# AVR_Board_4_0_Power_Supply.net
KiCad netlist of a schematic drawn in Altium Designer
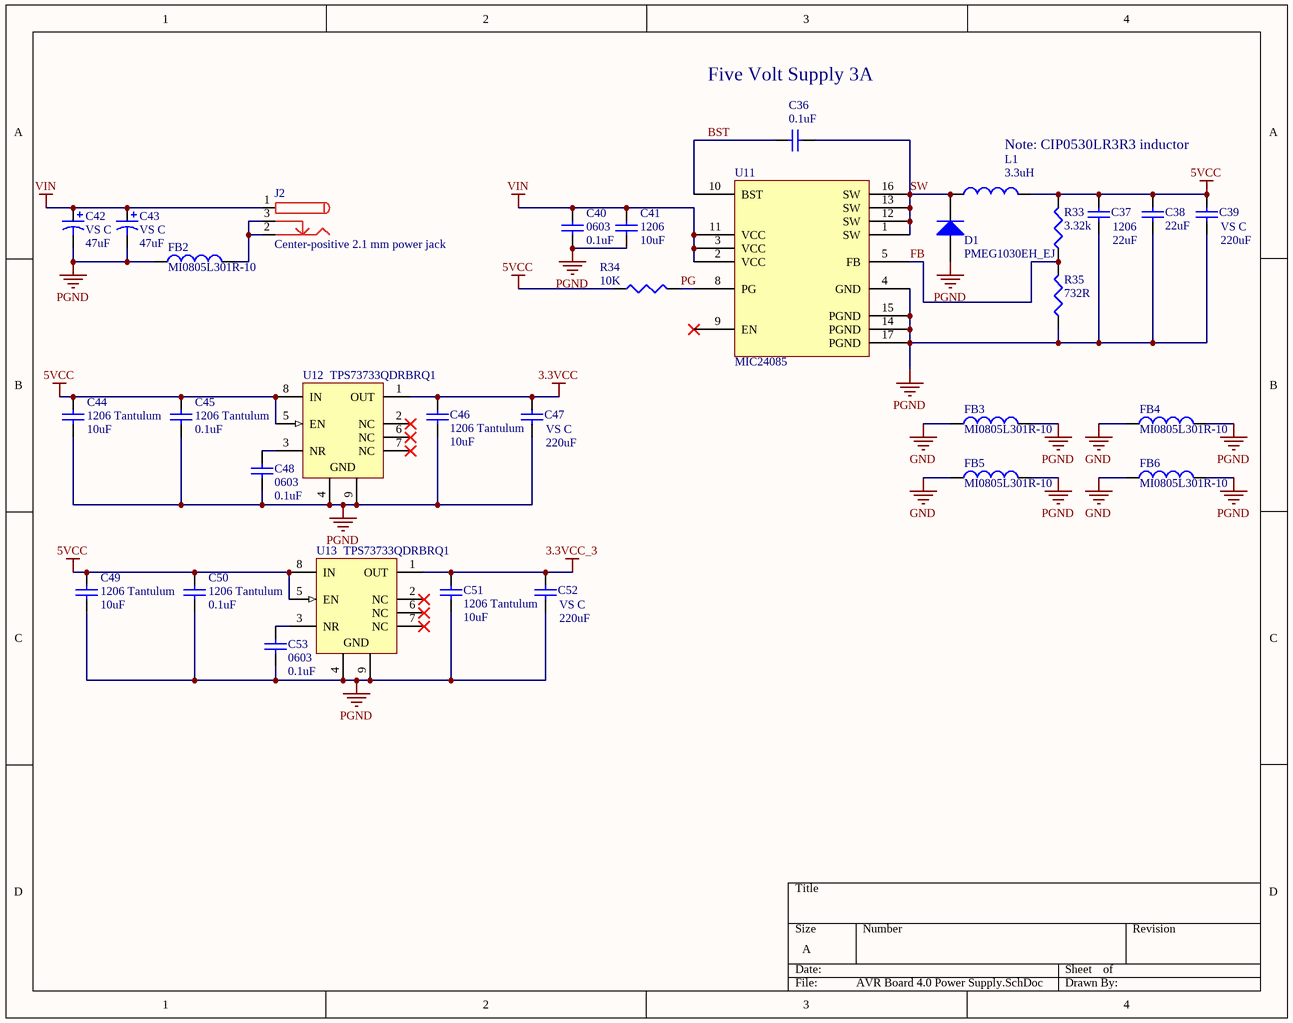
[diagram p0: AVR Board 4.0 Power Supply.SchDoc]

(export (version "E")
  (design (tool "Eeschema 10.0.6"))
  (components
    (comp (ref "C36")
      (value "0.1uF")
      (footprint "1608[0603]")
      (description "Capacitor (Semiconductor SIM Model)")
      (fields (field (name "Comment") "Cap Semi") (field (name "PUBLISHER") "Altium Limited"))
      (libsource (lib "Miscellaneous Devices") (part "Cap Semi"))
    )
    (comp (ref "C37")
      (value "1206")
      (footprint "C1206")
      (description "Capacitor (Semiconductor SIM Model)")
      (fields (field (name "ALTIUM_VALUE") "22uF") (field (name "PUBLISHER") "Altium Limited"))
      (libsource (lib "Miscellaneous Devices") (part "Cap Semi"))
    )
    (comp (ref "C38")
      (value "22uF")
      (footprint "C1206")
      (description "Capacitor (Semiconductor SIM Model)")
      (fields (field (name "Comment") "Cap Semi") (field (name "PUBLISHER") "Altium Limited"))
      (libsource (lib "Miscellaneous Devices") (part "Cap Semi"))
    )
    (comp (ref "C39")
      (value "VS C")
      (footprint "Panasonic VS C")
      (description "Capacitor (Semiconductor SIM Model)")
      (fields (field (name "ALTIUM_VALUE") "220uF") (field (name "PUBLISHER") "Altium Limited"))
      (libsource (lib "Miscellaneous Devices") (part "Cap Semi"))
    )
    (comp (ref "C40")
      (value "0603")
      (footprint "1608[0603]")
      (description "Capacitor (Semiconductor SIM Model)")
      (fields (field (name "ALTIUM_VALUE") "0.1uF") (field (name "PUBLISHER") "Altium Limited"))
      (libsource (lib "Miscellaneous Devices") (part "Cap Semi"))
    )
    (comp (ref "C41")
      (value "1206")
      (footprint "C1206")
      (description "Capacitor (Semiconductor SIM Model)")
      (fields (field (name "ALTIUM_VALUE") "10uF") (field (name "PUBLISHER") "Altium Limited"))
      (libsource (lib "Miscellaneous Devices") (part "Cap Semi"))
    )
    (comp (ref "C42")
      (value "VS C")
      (footprint "Panasonic VS C")
      (description "Polarized Capacitor (Surface Mount)")
      (fields (field (name "ALTIUM_VALUE") "47uF") (field (name "PUBLISHER") "Altium Limited"))
      (libsource (lib "Miscellaneous Devices") (part "Cap Pol3"))
    )
    (comp (ref "C43")
      (value "VS C")
      (footprint "Panasonic VS C")
      (description "Polarized Capacitor (Surface Mount)")
      (fields (field (name "ALTIUM_VALUE") "47uF") (field (name "PUBLISHER") "Altium Limited"))
      (libsource (lib "Miscellaneous Devices") (part "Cap Pol3"))
    )
    (comp (ref "C44")
      (value "1206 Tantulum")
      (footprint "C1206")
      (description "Capacitor (Semiconductor SIM Model)")
      (fields (field (name "ALTIUM_VALUE") "10uF") (field (name "PUBLISHER") "Altium Limited"))
      (libsource (lib "Miscellaneous Devices") (part "Cap Semi"))
    )
    (comp (ref "C45")
      (value "1206 Tantulum")
      (footprint "C1206")
      (description "Capacitor (Semiconductor SIM Model)")
      (fields (field (name "ALTIUM_VALUE") "0.1uF") (field (name "PUBLISHER") "Altium Limited"))
      (libsource (lib "Miscellaneous Devices") (part "Cap Semi"))
    )
    (comp (ref "C46")
      (value "1206 Tantulum")
      (footprint "C1206")
      (description "Capacitor (Semiconductor SIM Model)")
      (fields (field (name "ALTIUM_VALUE") "10uF") (field (name "PUBLISHER") "Altium Limited"))
      (libsource (lib "Miscellaneous Devices") (part "Cap Semi"))
    )
    (comp (ref "C47")
      (value "VS C")
      (footprint "Panasonic VS C")
      (description "Capacitor (Semiconductor SIM Model)")
      (fields (field (name "ALTIUM_VALUE") "220uF") (field (name "PUBLISHER") "Altium Limited"))
      (libsource (lib "Miscellaneous Devices") (part "Cap Semi"))
    )
    (comp (ref "C48")
      (value "0603")
      (footprint "1608[0603]")
      (description "Capacitor (Semiconductor SIM Model)")
      (fields (field (name "ALTIUM_VALUE") "0.1uF") (field (name "PUBLISHER") "Altium Limited"))
      (libsource (lib "Miscellaneous Devices") (part "Cap Semi"))
    )
    (comp (ref "C49")
      (value "1206 Tantulum")
      (footprint "C1206")
      (description "Capacitor (Semiconductor SIM Model)")
      (fields (field (name "ALTIUM_VALUE") "10uF") (field (name "PUBLISHER") "Altium Limited"))
      (libsource (lib "Miscellaneous Devices") (part "Cap Semi"))
    )
    (comp (ref "C50")
      (value "1206 Tantulum")
      (footprint "C1206")
      (description "Capacitor (Semiconductor SIM Model)")
      (fields (field (name "ALTIUM_VALUE") "0.1uF") (field (name "PUBLISHER") "Altium Limited"))
      (libsource (lib "Miscellaneous Devices") (part "Cap Semi"))
    )
    (comp (ref "C51")
      (value "1206 Tantulum")
      (footprint "C1206")
      (description "Capacitor (Semiconductor SIM Model)")
      (fields (field (name "ALTIUM_VALUE") "10uF") (field (name "PUBLISHER") "Altium Limited"))
      (libsource (lib "Miscellaneous Devices") (part "Cap Semi"))
    )
    (comp (ref "C52")
      (value "VS C")
      (footprint "Panasonic VS C")
      (description "Capacitor (Semiconductor SIM Model)")
      (fields (field (name "ALTIUM_VALUE") "220uF") (field (name "PUBLISHER") "Altium Limited"))
      (libsource (lib "Miscellaneous Devices") (part "Cap Semi"))
    )
    (comp (ref "C53")
      (value "0603")
      (footprint "1608[0603]")
      (description "Capacitor (Semiconductor SIM Model)")
      (fields (field (name "ALTIUM_VALUE") "0.1uF") (field (name "PUBLISHER") "Altium Limited"))
      (libsource (lib "Miscellaneous Devices") (part "Cap Semi"))
    )
    (comp (ref "D1")
      (value "PMEG1030EH_EJ")
      (footprint "PMEG1030EH_EJ")
      (description "Default Diode")
      (fields (field (name "PUBLISHER") "Altium Limited"))
      (libsource (lib "Miscellaneous Devices") (part "Diode"))
    )
    (comp (ref "FB2")
      (value "MI0805L301R-10")
      (footprint "SM 0805 - gap trimmed")
      (description "Inductor")
      (fields (field (name "PUBLISHER") "Altium Limited"))
      (libsource (lib "Miscellaneous Devices") (part "Inductor"))
    )
    (comp (ref "FB3")
      (value "MI0805L301R-10")
      (footprint "SM 0805 - gap trimmed")
      (description "Inductor")
      (fields (field (name "PUBLISHER") "Altium Limited"))
      (libsource (lib "Miscellaneous Devices") (part "Inductor"))
    )
    (comp (ref "FB4")
      (value "MI0805L301R-10")
      (footprint "SM 0805 - gap trimmed")
      (description "Inductor")
      (fields (field (name "PUBLISHER") "Altium Limited"))
      (libsource (lib "Miscellaneous Devices") (part "Inductor"))
    )
    (comp (ref "FB5")
      (value "MI0805L301R-10")
      (footprint "SM 0805 - gap trimmed")
      (description "Inductor")
      (fields (field (name "PUBLISHER") "Altium Limited"))
      (libsource (lib "Miscellaneous Devices") (part "Inductor"))
    )
    (comp (ref "FB6")
      (value "MI0805L301R-10")
      (footprint "SM 0805 - gap trimmed")
      (description "Inductor")
      (fields (field (name "PUBLISHER") "Altium Limited"))
      (libsource (lib "Miscellaneous Devices") (part "Inductor"))
    )
    (comp (ref "J2")
      (value "Center-positive 2.1 mm power jack")
      (footprint "PJ-102AH")
      (description "Power jack")
      (fields (field (name "PUBLISHER") "Altium Limited"))
      (libsource (lib "Adams Altium Library") (part "PWR2.5"))
    )
    (comp (ref "L1")
      (value "3.3uH")
      (footprint "CIP0530LR3R3")
      (description "Inductor")
      (fields (field (name "PUBLISHER") "Altium Limited"))
      (libsource (lib "Miscellaneous Devices") (part "Inductor"))
    )
    (comp (ref "R33")
      (value "3.32k")
      (footprint "J1-0603")
      (description "Resistor")
      (fields (field (name "Comment") "Res3") (field (name "PUBLISHER") "Altium Limited"))
      (libsource (lib "Miscellaneous Devices") (part "Res3"))
    )
    (comp (ref "R34")
      (value "10K")
      (footprint "J1-0603")
      (description "Resistor")
      (fields (field (name "Comment") "Res3") (field (name "PUBLISHER") "Altium Limited"))
      (libsource (lib "Miscellaneous Devices") (part "Res3"))
    )
    (comp (ref "R35")
      (value "732R")
      (footprint "J1-0603")
      (description "Resistor")
      (fields (field (name "Comment") "Res3") (field (name "PUBLISHER") "Altium Limited"))
      (libsource (lib "Miscellaneous Devices") (part "Res3"))
    )
    (comp (ref "U11")
      (value "MIC24085")
      (footprint "MIC24085-AYML")
      (libsource (lib "Adams Altium Library") (part "MIC24085"))
    )
    (comp (ref "U12")
      (value "TPS73733QDRBRQ1")
      (footprint "TI-DRB8-1750X1500TP_V")
      (fields (field (name "MANUFACTURER") "Texas Instruments"))
      (libsource (lib "TI Power Management Linear Regulator Single Channel LDO (400-7500mA)") (part "TPS73733QDRBRQ1"))
    )
    (comp (ref "U13")
      (value "TPS73733QDRBRQ1")
      (footprint "TI-DRB8-1750X1500TP_V")
      (fields (field (name "MANUFACTURER") "Texas Instruments"))
      (libsource (lib "TI Power Management Linear Regulator Single Channel LDO (400-7500mA)") (part "TPS73733QDRBRQ1"))
    )
  )
  (nets
    (net (code "1") (name "/BST") (class "Default")
      (node (ref "C36") (pin "2") (pinfunction "2_2") (pintype "passive"))
      (node (ref "U11") (pin "10") (pinfunction "BST_10") (pintype "passive"))
    )
    (net (code "2") (name "/FB") (class "Default")
      (node (ref "R33") (pin "1") (pinfunction "1_1") (pintype "passive"))
      (node (ref "R35") (pin "2") (pinfunction "2_2") (pintype "passive"))
      (node (ref "U11") (pin "5") (pinfunction "FB_5") (pintype "passive"))
    )
    (net (code "3") (name "/PG") (class "Default")
      (node (ref "R34") (pin "2") (pinfunction "2_2") (pintype "passive"))
      (node (ref "U11") (pin "8") (pinfunction "PG_8") (pintype "passive"))
    )
    (net (code "4") (name "/SW") (class "Default")
      (node (ref "C36") (pin "1") (pinfunction "1_1") (pintype "passive"))
      (node (ref "D1") (pin "2") (pinfunction "K_2") (pintype "passive"))
      (node (ref "L1") (pin "1") (pinfunction "1_1") (pintype "passive"))
      (node (ref "U11") (pin "1") (pinfunction "SW_1") (pintype "passive"))
      (node (ref "U11") (pin "12") (pinfunction "SW_12") (pintype "passive"))
      (node (ref "U11") (pin "13") (pinfunction "SW_13") (pintype "passive"))
      (node (ref "U11") (pin "16") (pinfunction "SW_16") (pintype "passive"))
    )
    (net (code "5") (name "3.3VCC") (class "Default")
      (node (ref "C46") (pin "1") (pinfunction "1_1") (pintype "passive"))
      (node (ref "C47") (pin "1") (pinfunction "1_1") (pintype "passive"))
      (node (ref "U12") (pin "1") (pinfunction "OUT_1") (pintype "power_in"))
    )
    (net (code "6") (name "3.3VCC_3") (class "Default")
      (node (ref "C51") (pin "1") (pinfunction "1_1") (pintype "passive"))
      (node (ref "C52") (pin "1") (pinfunction "1_1") (pintype "passive"))
      (node (ref "U13") (pin "1") (pinfunction "OUT_1") (pintype "power_in"))
    )
    (net (code "7") (name "5VCC") (class "Default")
      (node (ref "C37") (pin "2") (pinfunction "2_2") (pintype "passive"))
      (node (ref "C38") (pin "1") (pinfunction "1_1") (pintype "passive"))
      (node (ref "C39") (pin "1") (pinfunction "1_1") (pintype "passive"))
      (node (ref "C44") (pin "1") (pinfunction "1_1") (pintype "passive"))
      (node (ref "C45") (pin "2") (pinfunction "2_2") (pintype "passive"))
      (node (ref "C49") (pin "1") (pinfunction "1_1") (pintype "passive"))
      (node (ref "C50") (pin "2") (pinfunction "2_2") (pintype "passive"))
      (node (ref "L1") (pin "2") (pinfunction "2_2") (pintype "passive"))
      (node (ref "R33") (pin "2") (pinfunction "2_2") (pintype "passive"))
      (node (ref "R34") (pin "1") (pinfunction "1_1") (pintype "passive"))
      (node (ref "U12") (pin "5") (pinfunction "EN_5") (pintype "input"))
      (node (ref "U12") (pin "8") (pinfunction "IN_8") (pintype "power_in"))
      (node (ref "U13") (pin "5") (pinfunction "EN_5") (pintype "input"))
      (node (ref "U13") (pin "8") (pinfunction "IN_8") (pintype "power_in"))
    )
    (net (code "8") (name "GND") (class "Default")
      (node (ref "FB3") (pin "1") (pinfunction "1_1") (pintype "passive"))
      (node (ref "FB4") (pin "1") (pinfunction "1_1") (pintype "passive"))
      (node (ref "FB5") (pin "1") (pinfunction "1_1") (pintype "passive"))
      (node (ref "FB6") (pin "1") (pinfunction "1_1") (pintype "passive"))
    )
    (net (code "9") (name "Net-(FB2-Pad2)") (class "Default")
      (node (ref "FB2") (pin "2") (pinfunction "2_2") (pintype "passive"))
      (node (ref "J2") (pin "2") (pinfunction "2_2") (pintype "power_in"))
      (node (ref "J2") (pin "3") (pinfunction "3_3") (pintype "power_in"))
    )
    (net (code "10") (name "Net-(U12-NR)") (class "Default")
      (node (ref "C48") (pin "2") (pinfunction "2_2") (pintype "passive"))
      (node (ref "U12") (pin "3") (pinfunction "NR_3") (pintype "passive"))
    )
    (net (code "11") (name "Net-(U13-NR)") (class "Default")
      (node (ref "C53") (pin "2") (pinfunction "2_2") (pintype "passive"))
      (node (ref "U13") (pin "3") (pinfunction "NR_3") (pintype "passive"))
    )
    (net (code "12") (name "PGND") (class "Default")
      (node (ref "C37") (pin "1") (pinfunction "1_1") (pintype "passive"))
      (node (ref "C38") (pin "2") (pinfunction "2_2") (pintype "passive"))
      (node (ref "C39") (pin "2") (pinfunction "2_2") (pintype "passive"))
      (node (ref "C40") (pin "1") (pinfunction "1_1") (pintype "passive"))
      (node (ref "C41") (pin "1") (pinfunction "1_1") (pintype "passive"))
      (node (ref "C42") (pin "2") (pinfunction "2_2") (pintype "passive"))
      (node (ref "C43") (pin "2") (pinfunction "2_2") (pintype "passive"))
      (node (ref "C44") (pin "2") (pinfunction "2_2") (pintype "passive"))
      (node (ref "C45") (pin "1") (pinfunction "1_1") (pintype "passive"))
      (node (ref "C46") (pin "2") (pinfunction "2_2") (pintype "passive"))
      (node (ref "C47") (pin "2") (pinfunction "2_2") (pintype "passive"))
      (node (ref "C48") (pin "1") (pinfunction "1_1") (pintype "passive"))
      (node (ref "C49") (pin "2") (pinfunction "2_2") (pintype "passive"))
      (node (ref "C50") (pin "1") (pinfunction "1_1") (pintype "passive"))
      (node (ref "C51") (pin "2") (pinfunction "2_2") (pintype "passive"))
      (node (ref "C52") (pin "2") (pinfunction "2_2") (pintype "passive"))
      (node (ref "C53") (pin "1") (pinfunction "1_1") (pintype "passive"))
      (node (ref "D1") (pin "1") (pinfunction "A_1") (pintype "passive"))
      (node (ref "FB2") (pin "1") (pinfunction "1_1") (pintype "passive"))
      (node (ref "FB3") (pin "2") (pinfunction "2_2") (pintype "passive"))
      (node (ref "FB4") (pin "2") (pinfunction "2_2") (pintype "passive"))
      (node (ref "FB5") (pin "2") (pinfunction "2_2") (pintype "passive"))
      (node (ref "FB6") (pin "2") (pinfunction "2_2") (pintype "passive"))
      (node (ref "R35") (pin "1") (pinfunction "1_1") (pintype "passive"))
      (node (ref "U11") (pin "14") (pinfunction "PGND_14") (pintype "passive"))
      (node (ref "U11") (pin "15") (pinfunction "PGND_15") (pintype "passive"))
      (node (ref "U11") (pin "17") (pinfunction "PGND_17") (pintype "passive"))
      (node (ref "U11") (pin "4") (pinfunction "GND_4") (pintype "passive"))
      (node (ref "U12") (pin "4") (pinfunction "GND_4") (pintype "power_in"))
      (node (ref "U12") (pin "9") (pinfunction "GND_9") (pintype "power_in"))
      (node (ref "U13") (pin "4") (pinfunction "GND_4") (pintype "power_in"))
      (node (ref "U13") (pin "9") (pinfunction "GND_9") (pintype "power_in"))
    )
    (net (code "13") (name "VIN") (class "Default")
      (node (ref "C40") (pin "2") (pinfunction "2_2") (pintype "passive"))
      (node (ref "C41") (pin "2") (pinfunction "2_2") (pintype "passive"))
      (node (ref "C42") (pin "1") (pinfunction "1_1") (pintype "passive"))
      (node (ref "C43") (pin "1") (pinfunction "1_1") (pintype "passive"))
      (node (ref "J2") (pin "1") (pinfunction "1_1") (pintype "power_in"))
      (node (ref "U11") (pin "11") (pinfunction "VCC_11") (pintype "passive"))
      (node (ref "U11") (pin "2") (pinfunction "VCC_2") (pintype "passive"))
      (node (ref "U11") (pin "3") (pinfunction "VCC_3") (pintype "passive"))
    )
    (net (code "14") (name "unconnected-(U11-EN-Pad9)") (class "Default")
      (node (ref "U11") (pin "9") (pinfunction "EN_9") (pintype "passive+no_connect"))
    )
    (net (code "15") (name "unconnected-(U11-NC-Pad6)") (class "Default")
      (node (ref "U11") (pin "6") (pinfunction "NC_6") (pintype "passive"))
    )
    (net (code "16") (name "unconnected-(U11-NC-Pad7)") (class "Default")
      (node (ref "U11") (pin "7") (pinfunction "NC_7") (pintype "passive"))
    )
    (net (code "17") (name "unconnected-(U12-NC-Pad2)") (class "Default")
      (node (ref "U12") (pin "2") (pinfunction "NC_2") (pintype "passive+no_connect"))
    )
    (net (code "18") (name "unconnected-(U12-NC-Pad6)") (class "Default")
      (node (ref "U12") (pin "6") (pinfunction "NC_6") (pintype "passive+no_connect"))
    )
    (net (code "19") (name "unconnected-(U12-NC-Pad7)") (class "Default")
      (node (ref "U12") (pin "7") (pinfunction "NC_7") (pintype "passive+no_connect"))
    )
    (net (code "20") (name "unconnected-(U13-NC-Pad2)") (class "Default")
      (node (ref "U13") (pin "2") (pinfunction "NC_2") (pintype "passive+no_connect"))
    )
    (net (code "21") (name "unconnected-(U13-NC-Pad6)") (class "Default")
      (node (ref "U13") (pin "6") (pinfunction "NC_6") (pintype "passive+no_connect"))
    )
    (net (code "22") (name "unconnected-(U13-NC-Pad7)") (class "Default")
      (node (ref "U13") (pin "7") (pinfunction "NC_7") (pintype "passive+no_connect"))
    )
  )
)
